# TB_Power_supply_pcb.net
KiCad netlist of a schematic drawn in Altium Designer
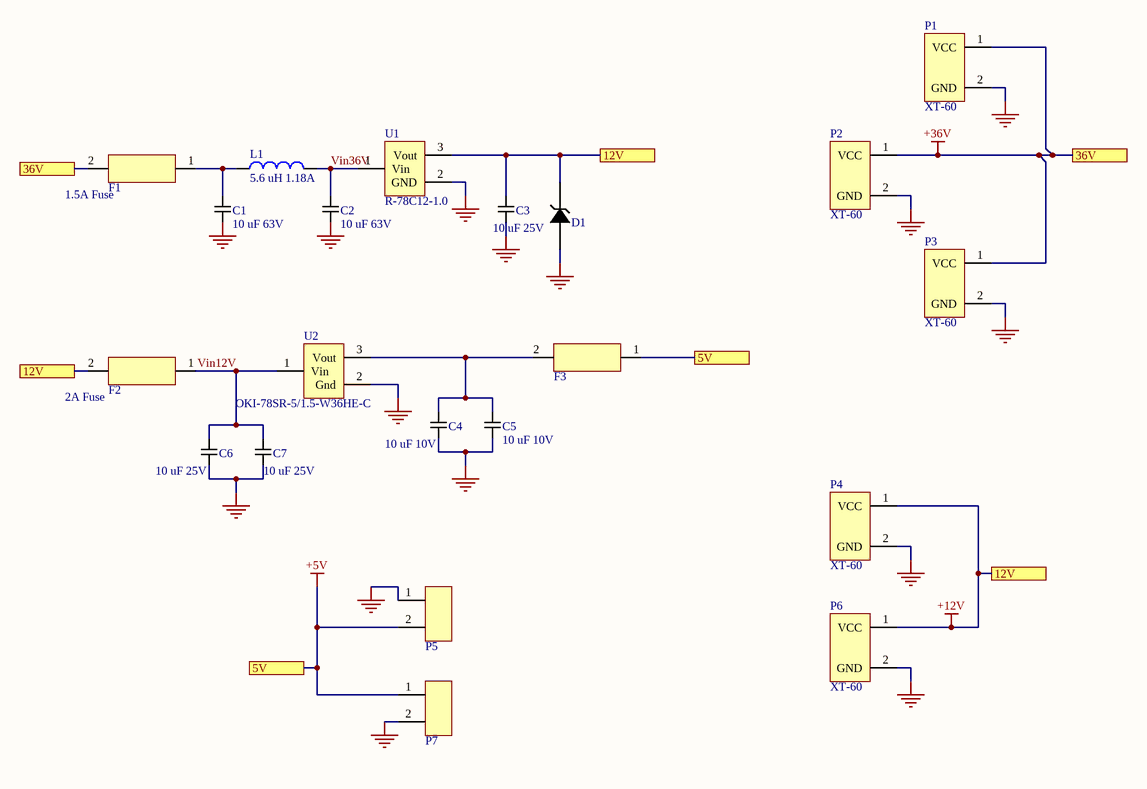
[diagram p0: TB Power supply pcb.SchDoc]

(export (version "E")
  (design (tool "Eeschema 10.0.6"))
  (components
    (comp (ref "C1")
      (value "10 uF 63V")
      (footprint "C_smd_3225")
      (fields (field (name "Comment") "SMD"))
      (libsource (lib "FF_component_lib") (part "C_SMD_3225"))
    )
    (comp (ref "C2")
      (value "10 uF 63V")
      (footprint "C_smd_3225")
      (fields (field (name "Comment") "SMD"))
      (libsource (lib "FF_component_lib") (part "C_SMD_3225"))
    )
    (comp (ref "C3")
      (value "10 uF 25V")
      (footprint "C_SMD_0805_pcb")
      (fields (field (name "Comment") "SMD"))
      (libsource (lib "FF_component_lib") (part "C_SMD_0805"))
    )
    (comp (ref "C4")
      (value "10 uF 10V")
      (footprint "C_SMD_0805_pcb")
      (fields (field (name "Comment") "SMD"))
      (libsource (lib "FF_component_lib") (part "C_SMD_0805"))
    )
    (comp (ref "C5")
      (value "10 uF 10V")
      (footprint "C_SMD_0805_pcb")
      (fields (field (name "Comment") "SMD"))
      (libsource (lib "FF_component_lib") (part "C_SMD_0805"))
    )
    (comp (ref "C6")
      (value "10 uF 25V")
      (footprint "C_SMD_0805_pcb")
      (fields (field (name "Comment") "SMD"))
      (libsource (lib "FF_component_lib") (part "C_SMD_0805"))
    )
    (comp (ref "C7")
      (value "10 uF 25V")
      (footprint "C_SMD_0805_pcb")
      (fields (field (name "Comment") "SMD"))
      (libsource (lib "FF_component_lib") (part "C_SMD_0805"))
    )
    (comp (ref "D1")
      (value "D_ZENER_smd_13V")
      (footprint "D_ZENER_12V_smd")
      (libsource (lib "FF_component_lib") (part "D_ZENER_smd_13V"))
    )
    (comp (ref "F1")
      (value "1.5A Fuse")
      (footprint "fuse_holder_3A")
      (description "(22.352mm x6.858mm)")
      (fields (field (name "Comment") "Fuse-holder-3A"))
      (libsource (lib "FF_component_lib") (part "Fuse-holder-3A"))
    )
    (comp (ref "F2")
      (value "2A Fuse")
      (footprint "fuse_holder_3A")
      (description "(22.352mm x6.858mm)")
      (fields (field (name "Comment") "Fuse-holder-3A"))
      (libsource (lib "FF_component_lib") (part "Fuse-holder-3A"))
    )
    (comp (ref "F3")
      (value "Fuse-holder-3A")
      (footprint "fuse_holder_3A")
      (description "(22.352mm x6.858mm)")
      (libsource (lib "FF_component_lib") (part "Fuse-holder-3A"))
    )
    (comp (ref "L1")
      (value "5.6 uH 1.18A")
      (footprint "L_1.18A_4532")
      (fields (field (name "Comment") "L_1.18A_4532"))
      (libsource (lib "FF_component_lib") (part "L_1.18A_4532"))
    )
    (comp (ref "P1") (value "XT-60") (footprint "XT-60") (libsource (lib "FF_component_lib") (part "XT-60")))
    (comp (ref "P2") (value "XT-60") (footprint "XT-60") (libsource (lib "FF_component_lib") (part "XT-60")))
    (comp (ref "P3") (value "XT-60") (footprint "XT-60") (libsource (lib "FF_component_lib") (part "XT-60")))
    (comp (ref "P4") (value "XT-60") (footprint "XT-60") (libsource (lib "FF_component_lib") (part "XT-60")))
    (comp (ref "P5")
      (value "JST_SE_2PIN")
      (footprint "JST_SE_2PIN")
      (libsource (lib "FF_component_lib") (part "JST_SE_2PIN"))
    )
    (comp (ref "P6") (value "XT-60") (footprint "XT-60") (libsource (lib "FF_component_lib") (part "XT-60")))
    (comp (ref "P7")
      (value "JST_SE_2PIN")
      (footprint "JST_SE_2PIN")
      (libsource (lib "FF_component_lib") (part "JST_SE_2PIN"))
    )
    (comp (ref "U1")
      (value "R-78C12-1.0")
      (footprint "R-78C12-1.0")
      (description "Wide input - 12V out buck")
      (libsource (lib "FF_component_lib") (part "R-78C12-1.0"))
    )
    (comp (ref "U2")
      (value "OKI-78SR-5/1.5-W36HE-C")
      (footprint "OKI-78SR-5/1.5-W36HE-C")
      (description "12V-5V buck")
      (libsource (lib "FF_component_lib") (part "OKI-78SR-5/1.5-W36HE-C"))
    )
  )
  (nets
    (net (code "1") (name "+5V") (class "Default")
      (node (ref "F3") (pin "1") (pinfunction "VIN_1") (pintype "passive"))
      (node (ref "P5") (pin "2") (pinfunction "2_2") (pintype "passive"))
      (node (ref "P7") (pin "1") (pinfunction "1_1") (pintype "passive"))
    )
    (net (code "2") (name "+12V") (class "Default")
      (node (ref "C3") (pin "1") (pinfunction "1_1") (pintype "passive"))
      (node (ref "D1") (pin "2") (pinfunction "2_2") (pintype "passive"))
      (node (ref "F2") (pin "2") (pinfunction "VIN_2") (pintype "passive"))
      (node (ref "P4") (pin "1") (pinfunction "VCC_1") (pintype "passive"))
      (node (ref "P6") (pin "1") (pinfunction "VCC_1") (pintype "passive"))
      (node (ref "U1") (pin "3") (pinfunction "Vout_3") (pintype "passive"))
    )
    (net (code "3") (name "+36V") (class "Default")
      (node (ref "F1") (pin "2") (pinfunction "VIN_2") (pintype "passive"))
      (node (ref "P1") (pin "1") (pinfunction "VCC_1") (pintype "passive"))
      (node (ref "P2") (pin "1") (pinfunction "VCC_1") (pintype "passive"))
      (node (ref "P3") (pin "1") (pinfunction "VCC_1") (pintype "passive"))
    )
    (net (code "4") (name "/Vin12V") (class "Default")
      (node (ref "C6") (pin "1") (pinfunction "1_1") (pintype "passive"))
      (node (ref "C7") (pin "1") (pinfunction "1_1") (pintype "passive"))
      (node (ref "F2") (pin "1") (pinfunction "VIN_1") (pintype "passive"))
      (node (ref "U2") (pin "1") (pinfunction "Vin_1") (pintype "passive"))
    )
    (net (code "5") (name "/Vin36V") (class "Default")
      (node (ref "C2") (pin "1") (pinfunction "1_1") (pintype "passive"))
      (node (ref "L1") (pin "2") (pinfunction "2_2") (pintype "passive"))
      (node (ref "U1") (pin "1") (pinfunction "Vin_1") (pintype "passive"))
    )
    (net (code "6") (name "GND") (class "Default")
      (node (ref "C1") (pin "2") (pinfunction "2_2") (pintype "passive"))
      (node (ref "C2") (pin "2") (pinfunction "2_2") (pintype "passive"))
      (node (ref "C3") (pin "2") (pinfunction "2_2") (pintype "passive"))
      (node (ref "C4") (pin "2") (pinfunction "2_2") (pintype "passive"))
      (node (ref "C5") (pin "2") (pinfunction "2_2") (pintype "passive"))
      (node (ref "C6") (pin "2") (pinfunction "2_2") (pintype "passive"))
      (node (ref "C7") (pin "2") (pinfunction "2_2") (pintype "passive"))
      (node (ref "D1") (pin "1") (pinfunction "56_1") (pintype "passive"))
      (node (ref "P1") (pin "2") (pinfunction "GND_2") (pintype "passive"))
      (node (ref "P2") (pin "2") (pinfunction "GND_2") (pintype "passive"))
      (node (ref "P3") (pin "2") (pinfunction "GND_2") (pintype "passive"))
      (node (ref "P4") (pin "2") (pinfunction "GND_2") (pintype "passive"))
      (node (ref "P5") (pin "1") (pinfunction "1_1") (pintype "passive"))
      (node (ref "P6") (pin "2") (pinfunction "GND_2") (pintype "passive"))
      (node (ref "P7") (pin "2") (pinfunction "2_2") (pintype "passive"))
      (node (ref "U1") (pin "2") (pinfunction "GND_2") (pintype "passive"))
      (node (ref "U2") (pin "2") (pinfunction "Gnd_2") (pintype "passive"))
    )
    (net (code "7") (name "Net-(C1-Pad1)") (class "Default")
      (node (ref "C1") (pin "1") (pinfunction "1_1") (pintype "passive"))
      (node (ref "F1") (pin "1") (pinfunction "VIN_1") (pintype "passive"))
      (node (ref "L1") (pin "1") (pinfunction "1_1") (pintype "passive"))
    )
    (net (code "8") (name "Net-(U2-Vout)") (class "Default")
      (node (ref "C4") (pin "1") (pinfunction "1_1") (pintype "passive"))
      (node (ref "C5") (pin "1") (pinfunction "1_1") (pintype "passive"))
      (node (ref "F3") (pin "2") (pinfunction "VIN_2") (pintype "passive"))
      (node (ref "U2") (pin "3") (pinfunction "Vout_3") (pintype "passive"))
    )
  )
)
